# Sheet2.net
KiCad netlist of a schematic drawn in Altium Designer
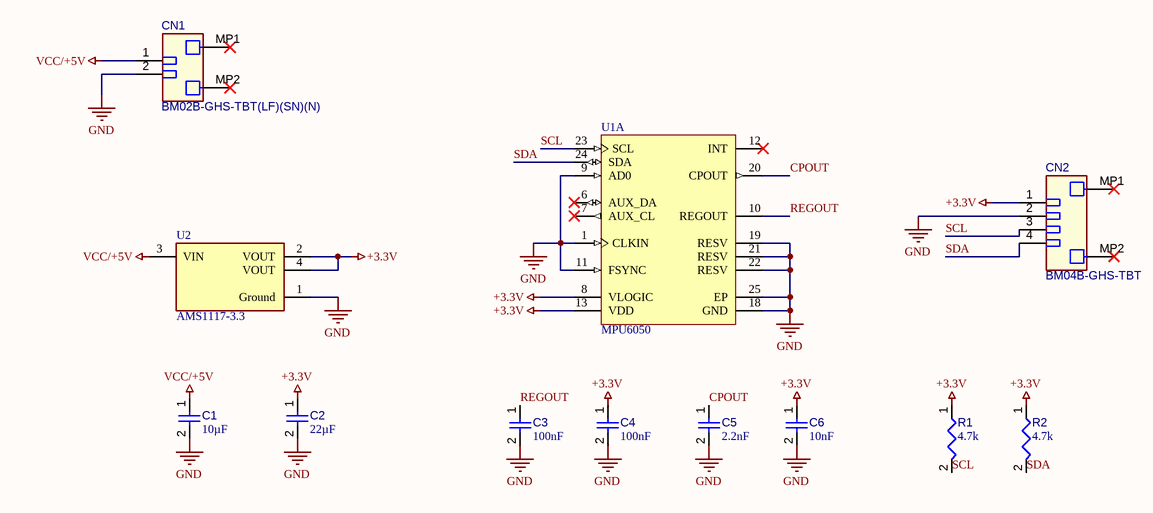
[diagram p0: Sheet2.SchDoc]

(export (version "E")
  (design (tool "Eeschema 10.0.6"))
  (components
    (comp (ref "C1")
      (value "10µF")
      (footprint "CAPC0603(1608)100_L")
      (description "Chip Capacitor, 10µF +/-20%, 10V, 0603, Thickness 1 mm")
      (fields (field (name "TOLERANCE") "10%") (field (name "Comment") "Capacitor 10µF +/-20% 10V 0603"))
      (libsource (lib "NMECAGNI") (part "CAP-NP-2"))
    )
    (comp (ref "C2")
      (value "22µF")
      (footprint "CAPC0805(2012)145_L")
      (description "Chip Capacitor, 22µF +/-40%, 16V, 0805, Thickness 1.45 mm")
      (fields (field (name "TOLERANCE") "5%") (field (name "Comment") "Capacitor 22µF +/-40% 16V 0805"))
      (libsource (lib "NMECAGNI") (part "CAP-NP-2"))
    )
    (comp (ref "C3")
      (value "100nF")
      (footprint "CAPC1005X56X25LL10T15")
      (description "Chip Capacitor, 0.1 uF, +/- 5%, 16 V, 0402 (1005 Metric)")
      (fields (field (name "TOLERANCE") "5%") (field (name "Comment") "Capacitor 0.1 uF +/- 5% 16 V 0402"))
      (libsource (lib "NMECAGNI") (part "CAP-NP-2"))
    )
    (comp (ref "C4")
      (value "100nF")
      (footprint "CAPC1005X56X25LL10T15")
      (description "Chip Capacitor, 0.1 uF, +/- 5%, 16 V, 0402 (1005 Metric)")
      (fields (field (name "TOLERANCE") "5%") (field (name "Comment") "Capacitor 0.1 uF +/- 5% 16 V 0402"))
      (libsource (lib "NMECAGNI") (part "CAP-NP-2"))
    )
    (comp (ref "C5")
      (value "2.2nF")
      (footprint "CAPC0402(1005)60_L")
      (description "Chip Capacitor, 2,2µF +/-20%, 10V, 0402, Thickness 0.6 mm")
      (fields (field (name "TOLERANCE") "10%") (field (name "Comment") "Capacitor 2,2µF +/-20% 10V 0402"))
      (libsource (lib "NMECAGNI") (part "CAP-NP-2"))
    )
    (comp (ref "C6")
      (value "10nF")
      (footprint "CAPC0402(1005)60_L")
      (description "Chip Capacitor, 2,2µF +/-20%, 10V, 0402, Thickness 0.6 mm")
      (fields (field (name "TOLERANCE") "10%") (field (name "Comment") "Capacitor 2,2µF +/-20% 10V 0402"))
      (libsource (lib "NMECAGNI") (part "CAP-NP-2"))
    )
    (comp (ref "CN1")
      (value "BM02B-GHS-TBT(LF)(SN)(N)")
      (footprint "JST-BM02B-GHS-TBT_V")
      (libsource (lib "NMECAGNI") (part "CMP-00144-3"))
    )
    (comp (ref "CN2")
      (value "BM04B-GHS-TBT")
      (footprint "JST-BM04B-GHS-TBT_V")
      (description "Header, Pitch 1.25 mm, 1 x 4 Position, Height 4.05 mm, -25 to 85 degC")
      (libsource (lib "NMECAGNI") (part "CMP-00071-3"))
    )
    (comp (ref "R1")
      (value "4.7k")
      (footprint "RESC0805(2012)_L")
      (description "470R 0.125W 5% 0805 (2012 Metric)  SMD")
      (fields (field (name "POWER") "125mW") (field (name "TOLERANCE") "5%"))
      (libsource (lib "NMECAGNI") (part "470R5J"))
    )
    (comp (ref "R2")
      (value "4.7k")
      (footprint "RESC0805(2012)_L")
      (description "470R 0.125W 5% 0805 (2012 Metric)  SMD")
      (fields (field (name "POWER") "125mW") (field (name "TOLERANCE") "5%"))
      (libsource (lib "NMECAGNI") (part "470R5J"))
    )
    (comp (ref "U1")
      (value "MPU6050")
      (footprint "INSE-QFN-24_V")
      (fields (field (name "MANUFACTURER") "InvenSense"))
      (libsource (lib "NMECAGNI") (part "INSE-MPU6050-QFN-24"))
    )
    (comp (ref "U2")
      (value "AMS1117-3.3")
      (footprint "FP-AMS1117-IPC_C")
      (description "LDO Voltage Regulators 1A, 3.3V")
      (fields
        (field (name "OCTOPART") "https://octopart.com/ams1117-3.3-advanced+monolithic+systems-25899300")
        (field (name "MANUFACTURER") "Advanced Monolithic Systems")
      )
      (libsource (lib "Altium Content Vault") (part "8bdbb5f8e77002000e30dd2845d0354"))
    )
  )
  (nets
    (net (code "1") (name "+3.3V") (class "Default")
      (node (ref "C2") (pin "1") (pinfunction "1_1") (pintype "passive"))
      (node (ref "C4") (pin "1") (pinfunction "1_1") (pintype "passive"))
      (node (ref "C6") (pin "1") (pinfunction "1_1") (pintype "passive"))
      (node (ref "CN2") (pin "1") (pinfunction "1_1") (pintype "passive"))
      (node (ref "R1") (pin "1") (pinfunction "1_1") (pintype "passive"))
      (node (ref "R2") (pin "1") (pinfunction "1_1") (pintype "passive"))
      (node (ref "U1") (pin "13") (pinfunction "VDD_13") (pintype "power_in"))
      (node (ref "U1") (pin "8") (pinfunction "VLOGIC_8") (pintype "power_in"))
      (node (ref "U2") (pin "2") (pinfunction "VOUT_2") (pintype "passive"))
      (node (ref "U2") (pin "4") (pinfunction "VOUT_4") (pintype "passive"))
    )
    (net (code "2") (name "/CPOUT") (class "Default")
      (node (ref "C5") (pin "1") (pinfunction "1_1") (pintype "passive"))
      (node (ref "U1") (pin "20") (pinfunction "CPOUT_20") (pintype "output"))
    )
    (net (code "3") (name "/REGOUT") (class "Default")
      (node (ref "C3") (pin "1") (pinfunction "1_1") (pintype "passive"))
      (node (ref "U1") (pin "10") (pinfunction "REGOUT_10") (pintype "passive"))
    )
    (net (code "4") (name "/SCL") (class "Default")
      (node (ref "CN2") (pin "3") (pinfunction "3_3") (pintype "passive"))
      (node (ref "R1") (pin "2") (pinfunction "2_2") (pintype "passive"))
      (node (ref "U1") (pin "23") (pinfunction "SCL_23") (pintype "input"))
    )
    (net (code "5") (name "/SDA") (class "Default")
      (node (ref "CN2") (pin "4") (pinfunction "4_4") (pintype "passive"))
      (node (ref "R2") (pin "2") (pinfunction "2_2") (pintype "passive"))
      (node (ref "U1") (pin "24") (pinfunction "SDA_24") (pintype "bidirectional"))
    )
    (net (code "6") (name "GND") (class "Default")
      (node (ref "C1") (pin "2") (pinfunction "2_2") (pintype "passive"))
      (node (ref "C2") (pin "2") (pinfunction "2_2") (pintype "passive"))
      (node (ref "C3") (pin "2") (pinfunction "2_2") (pintype "passive"))
      (node (ref "C4") (pin "2") (pinfunction "2_2") (pintype "passive"))
      (node (ref "C5") (pin "2") (pinfunction "2_2") (pintype "passive"))
      (node (ref "C6") (pin "2") (pinfunction "2_2") (pintype "passive"))
      (node (ref "CN1") (pin "2") (pinfunction "2_2") (pintype "passive"))
      (node (ref "CN2") (pin "2") (pinfunction "2_2") (pintype "passive"))
      (node (ref "U1") (pin "1") (pinfunction "CLKIN_1") (pintype "input"))
      (node (ref "U1") (pin "11") (pinfunction "FSYNC_11") (pintype "input"))
      (node (ref "U1") (pin "18") (pinfunction "GND_18") (pintype "power_in"))
      (node (ref "U1") (pin "19") (pinfunction "RESV_19") (pintype "passive"))
      (node (ref "U1") (pin "21") (pinfunction "RESV_21") (pintype "passive"))
      (node (ref "U1") (pin "22") (pinfunction "RESV_22") (pintype "passive"))
      (node (ref "U1") (pin "25") (pinfunction "EP_25") (pintype "passive"))
      (node (ref "U1") (pin "9") (pinfunction "AD0_9") (pintype "input"))
      (node (ref "U2") (pin "1") (pinfunction "Ground_1") (pintype "power_in"))
    )
    (net (code "7") (name "VCC{slash}+5V") (class "Default")
      (node (ref "C1") (pin "1") (pinfunction "1_1") (pintype "passive"))
      (node (ref "CN1") (pin "1") (pinfunction "1_1") (pintype "passive"))
      (node (ref "U2") (pin "3") (pinfunction "VIN_3") (pintype "power_in"))
    )
    (net (code "8") (name "unconnected-(CN1-PadMP1)") (class "Default")
      (node (ref "CN1") (pin "MP1") (pinfunction "MP1_MP1") (pintype "passive+no_connect"))
    )
    (net (code "9") (name "unconnected-(CN1-PadMP2)") (class "Default")
      (node (ref "CN1") (pin "MP2") (pinfunction "MP2_MP2") (pintype "passive+no_connect"))
    )
    (net (code "10") (name "unconnected-(CN2-PadMP1)") (class "Default")
      (node (ref "CN2") (pin "MP1") (pinfunction "MP1_MP1") (pintype "passive+no_connect"))
    )
    (net (code "11") (name "unconnected-(CN2-PadMP2)") (class "Default")
      (node (ref "CN2") (pin "MP2") (pinfunction "MP2_MP2") (pintype "passive+no_connect"))
    )
    (net (code "12") (name "unconnected-(U1A-AUX_CL-Pad7)") (class "Default")
      (node (ref "U1") (pin "7") (pinfunction "AUX_CL_7") (pintype "output+no_connect"))
    )
    (net (code "13") (name "unconnected-(U1A-AUX_DA-Pad6)") (class "Default")
      (node (ref "U1") (pin "6") (pinfunction "AUX_DA_6") (pintype "bidirectional+no_connect"))
    )
    (net (code "14") (name "unconnected-(U1A-INT-Pad12)") (class "Default")
      (node (ref "U1") (pin "12") (pinfunction "INT_12") (pintype "open_collector+no_connect"))
    )
  )
)
